# Micro_Card.net
KiCad netlist of a schematic drawn in Altium Designer
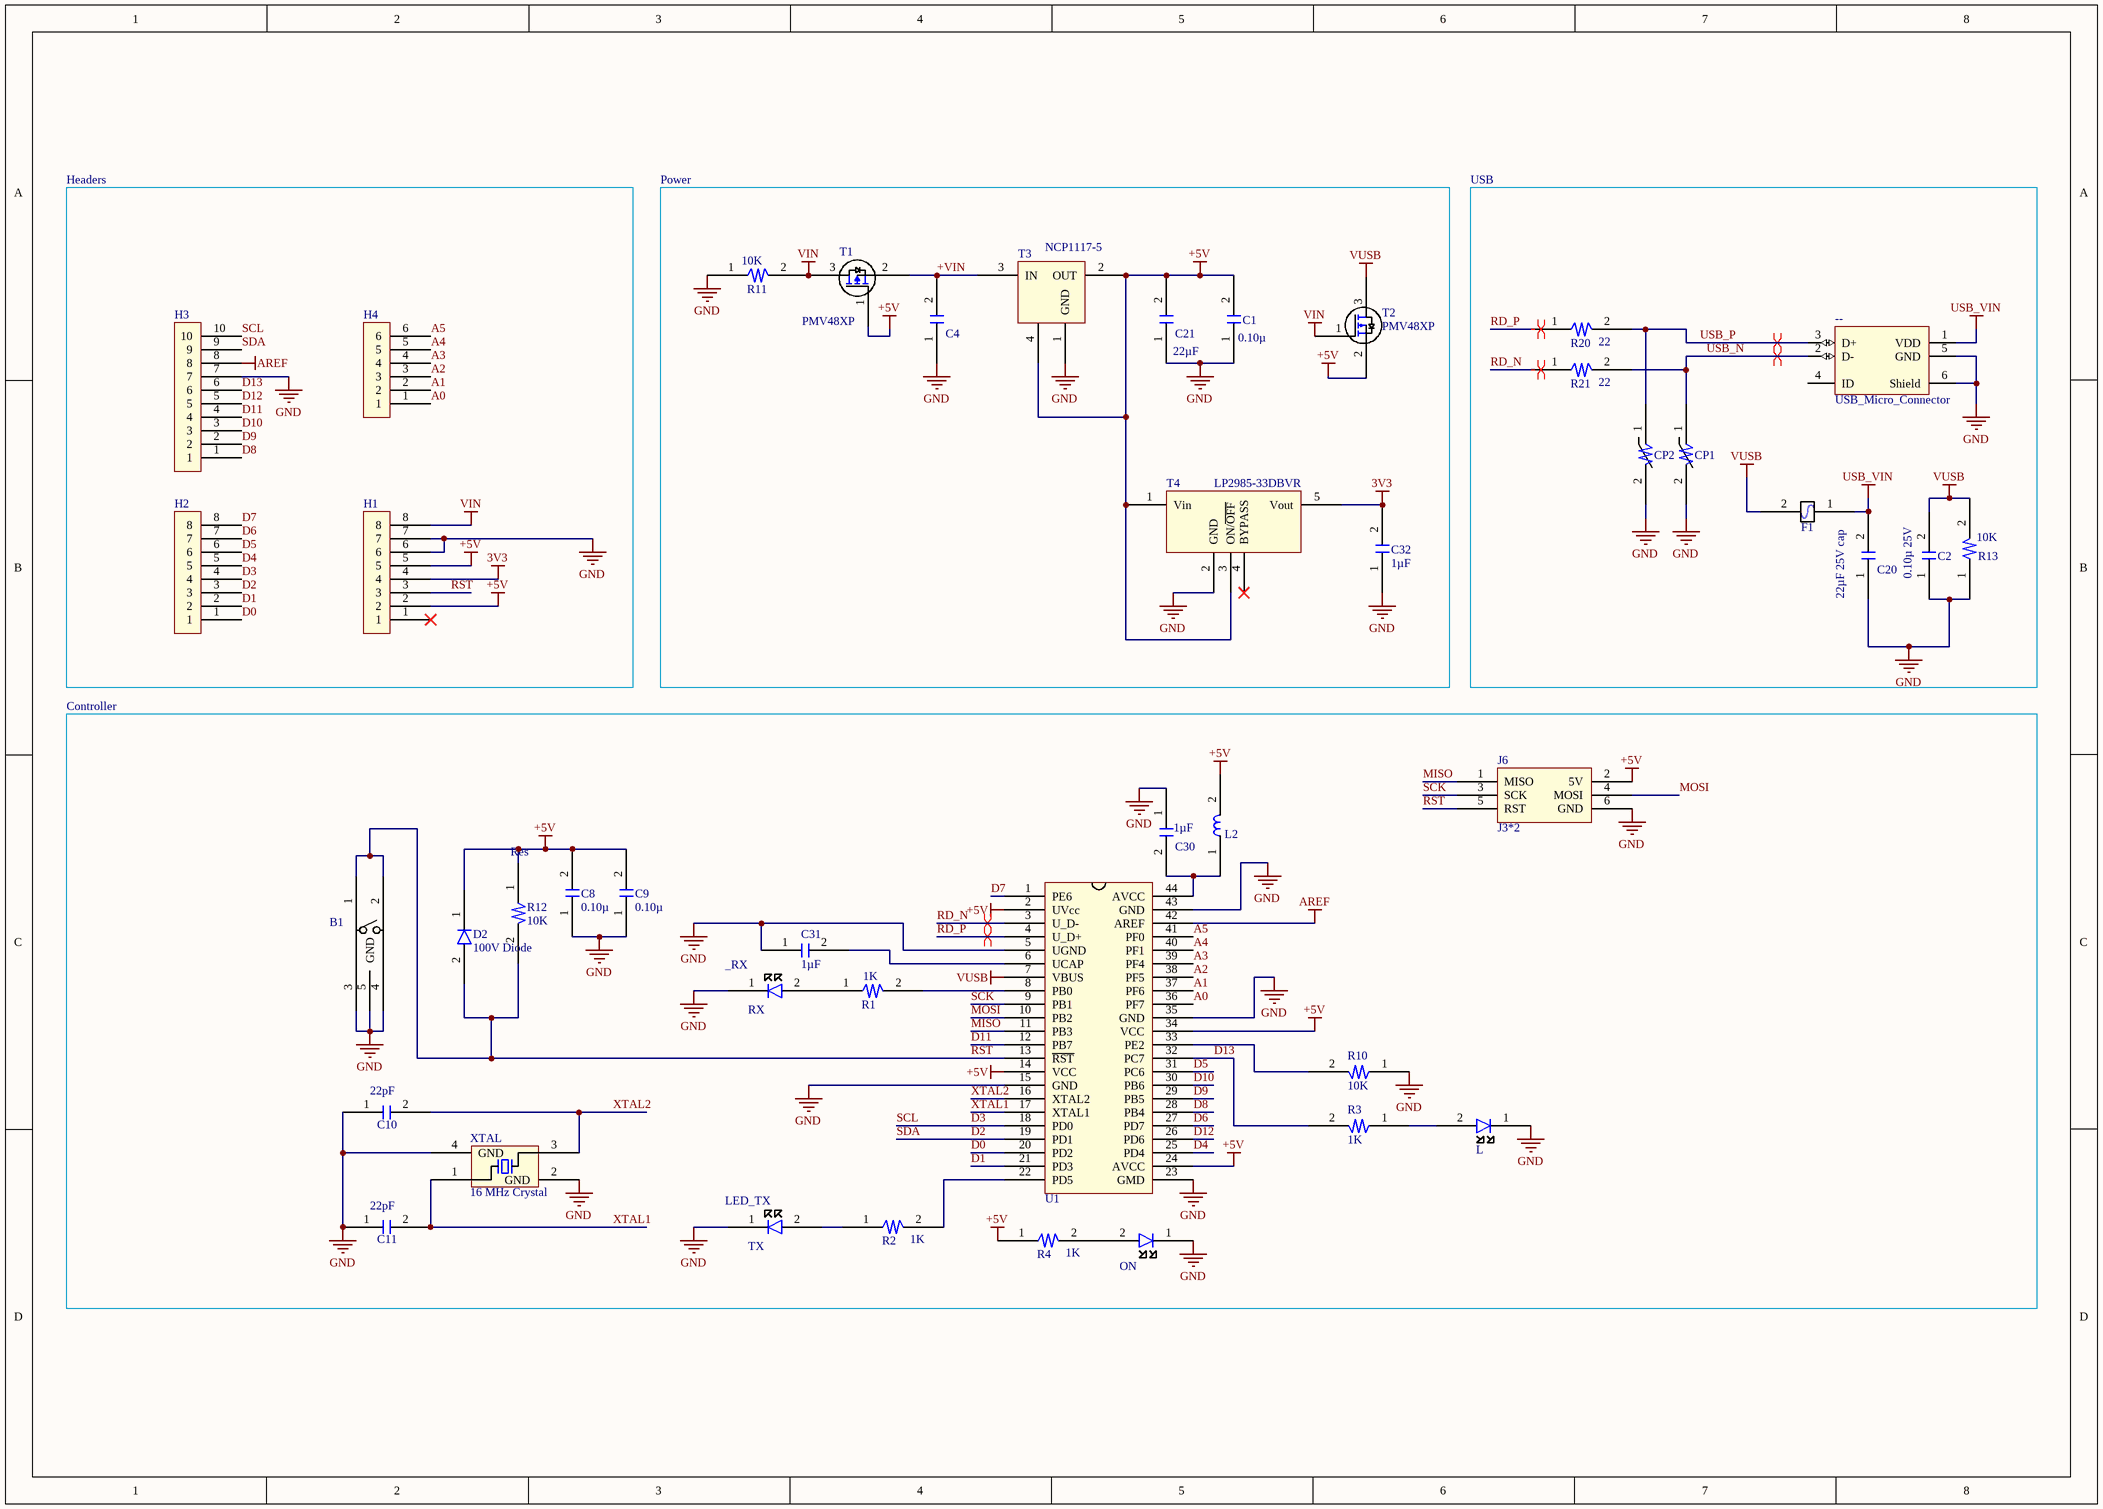
[diagram p0: Micro_Card.SchDoc]

(export (version "E")
  (design (tool "Eeschema 10.0.6"))
  (components
    (comp (ref "--")
      (value "USB_Micro_Connector")
      (footprint "USB_micro_through")
      (description "CONN USB MICRO B RECPT SMT R/A")
      (fields
        (field (name "MANUFACTURER PART NUMBER") "10118194-0001LF")
        (field (name "01 CREATED BY") "David Lynch @ 30/11/2017")
        (field (name "02 REVIEWED BY") "Rodrigo Maureira @ 14/01/2018")
      )
      (libsource (lib "Micro_Schlib") (part "USB_micro_through"))
    )
    (comp (ref "B1")
      (value "off-mom")
      (footprint "450-1760")
      (description "Tactile Button")
      (libsource (lib "Micro_Schlib") (part "Button"))
    )
    (comp (ref "C1")
      (value "0.10µ")
      (footprint "R15_0805_cap_M")
      (description "Cap.")
      (libsource (lib "Micro_Schlib") (part "0.10µF 25V Cap"))
    )
    (comp (ref "C2")
      (value "0.10µ 25V")
      (footprint "R15_0805_cap_M")
      (description "Cap.")
      (libsource (lib "Micro_Schlib") (part "0.10µF 25V Cap"))
    )
    (comp (ref "C4")
      (value "0.10µF ±10% 25V Ceramic Capacitor X7R 0805 (2012 Metric)")
      (footprint "R15_0805_cap_M")
      (description "Cap.")
      (libsource (lib "Micro_Schlib") (part "0.10µF ±10% 25V cap"))
    )
    (comp (ref "C8")
      (value "0.10µ")
      (footprint "R15_0805_cap_M")
      (description "Cap.")
      (libsource (lib "Micro_Schlib") (part "0.10µF 25V Cap"))
    )
    (comp (ref "C9")
      (value "0.10µ")
      (footprint "R15_0805_cap_M")
      (description "Cap.")
      (libsource (lib "Micro_Schlib") (part "0.10µF 25V Cap"))
    )
    (comp (ref "C10")
      (value "22pF")
      (footprint "R15_0805_cap_M")
      (description "Cap.")
      (libsource (lib "Micro_Schlib") (part "22pF 50V cap"))
    )
    (comp (ref "C11")
      (value "22pF")
      (footprint "R15_0805_cap_M")
      (description "Cap.")
      (libsource (lib "Micro_Schlib") (part "22pF 50V cap"))
    )
    (comp (ref "C20")
      (value "22µF 25V cap")
      (footprint "X5R_22uF_25v_1206_X_M")
      (description "Cap.")
      (libsource (lib "Micro_Schlib") (part "22µF 25V cap"))
    )
    (comp (ref "C21")
      (value "22µF")
      (footprint "X5R_22uF_25v_1206_X_M")
      (description "Cap.")
      (libsource (lib "Micro_Schlib") (part "22µF 25V cap"))
    )
    (comp (ref "C30")
      (value "1µF")
      (footprint "C2012_M")
      (description "Cap.")
      (libsource (lib "Micro_Schlib") (part "1µF 50V cap"))
    )
    (comp (ref "C31")
      (value "1µF")
      (footprint "C2012_M")
      (description "Cap.")
      (libsource (lib "Micro_Schlib") (part "1µF 50V cap"))
    )
    (comp (ref "C32")
      (value "1µF")
      (footprint "C2012_M")
      (description "Cap.")
      (libsource (lib "Micro_Schlib") (part "1µF 50V cap"))
    )
    (comp (ref "CP1")
      (value "Gard Resistor")
      (footprint "UltraGuard 0805")
      (libsource (lib "Micro_Schlib") (part "Gard Resistor"))
    )
    (comp (ref "CP2")
      (value "Gard Resistor")
      (footprint "UltraGuard 0805")
      (libsource (lib "Micro_Schlib") (part "Gard Resistor"))
    )
    (comp (ref "D2")
      (value "100V Diode")
      (footprint "CD1206-S01575")
      (description "Standard Diode")
      (libsource (lib "Micro_Schlib") (part "CD1206 - S01575"))
    )
    (comp (ref "F1")
      (value "MF-MSF0502")
      (footprint "MF-MSMF050_M")
      (description "Resetable fuse")
      (libsource (lib "Micro_Schlib") (part "MF-MSF0502"))
    )
    (comp (ref "H1")
      (value "H8")
      (footprint "H8")
      (description "Header")
      (libsource (lib "Micro_Schlib") (part "H8"))
    )
    (comp (ref "H2")
      (value "H8")
      (footprint "H8")
      (description "Header")
      (libsource (lib "Micro_Schlib") (part "H8"))
    )
    (comp (ref "H3")
      (value "H10")
      (footprint "H10")
      (description "Header")
      (libsource (lib "Micro_Schlib") (part "H10"))
    )
    (comp (ref "H4")
      (value "H6")
      (footprint "H6")
      (description "Header")
      (libsource (lib "Micro_Schlib") (part "H6"))
    )
    (comp (ref "J6")
      (value "J3*2")
      (footprint "J3*2")
      (description "Header")
      (libsource (lib "Micro_Schlib") (part "J3*2"))
    )
    (comp (ref "L")
      (value "LED_L")
      (footprint "Wurth led 0805")
      (description "LED clear")
      (libsource (lib "Micro_Schlib") (part "LED"))
    )
    (comp (ref "L2")
      (value "MH2029 - 300Y")
      (footprint "MH2029-300YC")
      (description "Ferite Bead")
      (libsource (lib "Micro_Schlib") (part "MH2029 - 300Y"))
    )
    (comp (ref "ON")
      (value "LED_ON")
      (footprint "Wurth led 0805")
      (description "LED clear")
      (libsource (lib "Micro_Schlib") (part "LED"))
    )
    (comp (ref "R1")
      (value "1K")
      (footprint "RNCP0805_M")
      (description "Res.")
      (fields (field (name "Comment") "Res"))
      (libsource (lib "Micro_Schlib") (part "Res"))
    )
    (comp (ref "R2")
      (value "1K")
      (footprint "RNCP0805_M")
      (description "Res.")
      (fields (field (name "Comment") "Res"))
      (libsource (lib "Micro_Schlib") (part "Res"))
    )
    (comp (ref "R3")
      (value "1K")
      (footprint "RNCP0805_M")
      (description "Res.")
      (fields (field (name "Comment") "Res"))
      (libsource (lib "Micro_Schlib") (part "Res"))
    )
    (comp (ref "R4")
      (value "1K")
      (footprint "RNCP0805_M")
      (description "Res.")
      (libsource (lib "Micro_Schlib") (part "Res"))
    )
    (comp (ref "R10")
      (value "10K")
      (footprint "RNCP0805_M")
      (description "Res.")
      (libsource (lib "Micro_Schlib") (part "Res"))
    )
    (comp (ref "R11")
      (value "10K")
      (footprint "RNCP0805_M")
      (description "Res.")
      (fields (field (name "Comment") "Res"))
      (libsource (lib "Micro_Schlib") (part "Res"))
    )
    (comp (ref "R12")
      (value "Res")
      (footprint "RNCP0805_M")
      (description "Res.")
      (fields (field (name "ALTIUM_VALUE") "10K"))
      (libsource (lib "Micro_Schlib") (part "Res"))
    )
    (comp (ref "R13")
      (value "10K")
      (footprint "RNCP0805_M")
      (description "Res.")
      (libsource (lib "Micro_Schlib") (part "Res"))
    )
    (comp (ref "R20")
      (value "22")
      (footprint "RNCP0805_M")
      (description "Res.")
      (libsource (lib "Micro_Schlib") (part "Res"))
    )
    (comp (ref "R21")
      (value "22")
      (footprint "RNCP0805_M")
      (description "Res.")
      (libsource (lib "Micro_Schlib") (part "Res"))
    )
    (comp (ref "RX")
      (value "_RX")
      (footprint "Wurth led 0805")
      (description "LED clear")
      (libsource (lib "Micro_Schlib") (part "LED"))
    )
    (comp (ref "T1")
      (value "PMV48XP")
      (footprint "PMV48XP_SOT23")
      (description "P type MOSFET")
      (libsource (lib "") (part "PMV48XP_1"))
    )
    (comp (ref "T2")
      (value "PMV48XP")
      (footprint "PMV48XP_SOT23")
      (description "P type MOSFET")
      (libsource (lib "Micro_Schlib") (part "PMV48XP"))
    )
    (comp (ref "T3")
      (value "NCP1117-5")
      (footprint "NCP1117_SOT223")
      (description "5V reg")
      (libsource (lib "Micro_Schlib") (part "NCP1117-5"))
    )
    (comp (ref "T4")
      (value "LP2985-33DBVR")
      (footprint "LP2985_SOT23_M")
      (description "3.3V reg")
      (libsource (lib "Micro_Schlib") (part "LP2985-33DBVR"))
    )
    (comp (ref "TX")
      (value "LED_TX")
      (footprint "Wurth led 0805")
      (description "LED clear")
      (libsource (lib "Micro_Schlib") (part "LED"))
    )
    (comp (ref "U1")
      (value "ATmega32U4")
      (footprint "ATmega32u4_TQFP44")
      (libsource (lib "Micro_Schlib") (part "ATmega32U4"))
    )
    (comp (ref "XTAL")
      (value "16 MHz Crystal")
      (footprint "TSX-3225")
      (description "Crystal")
      (libsource (lib "Micro_Schlib") (part "16 MHz Crystal"))
    )
  )
  (nets
    (net (code "1") (name "+5V") (class "Default")
      (node (ref "C1") (pin "2") (pinfunction "2_2") (pintype "passive"))
      (node (ref "C21") (pin "2") (pinfunction "2_2") (pintype "passive"))
      (node (ref "C8") (pin "2") (pinfunction "2_2") (pintype "passive"))
      (node (ref "C9") (pin "2") (pinfunction "2_2") (pintype "passive"))
      (node (ref "D2") (pin "1") (pinfunction "1_1") (pintype "passive"))
      (node (ref "H1") (pin "2") (pinfunction "2_2") (pintype "passive"))
      (node (ref "H1") (pin "5") (pinfunction "5_5") (pintype "passive"))
      (node (ref "J6") (pin "2") (pinfunction "5V_2") (pintype "passive"))
      (node (ref "L2") (pin "2") (pinfunction "2_2") (pintype "passive"))
      (node (ref "R12") (pin "1") (pinfunction "1_1") (pintype "passive"))
      (node (ref "R4") (pin "1") (pinfunction "1_1") (pintype "passive"))
      (node (ref "T1") (pin "1") (pinfunction "G_1") (pintype "passive"))
      (node (ref "T2") (pin "2") (pinfunction "S_2") (pintype "passive"))
      (node (ref "T3") (pin "2") (pinfunction "OUT_2") (pintype "passive"))
      (node (ref "T3") (pin "4") (pinfunction "tab_4") (pintype "passive"))
      (node (ref "T4") (pin "1") (pinfunction "Vin_1") (pintype "passive"))
      (node (ref "T4") (pin "3") (pinfunction "ON/~{OFF}_3") (pintype "passive"))
      (node (ref "U1") (pin "14") (pinfunction "VCC_14") (pintype "passive"))
      (node (ref "U1") (pin "2") (pinfunction "UVcc_2") (pintype "passive"))
      (node (ref "U1") (pin "24") (pinfunction "AVCC_24") (pintype "passive"))
      (node (ref "U1") (pin "34") (pinfunction "VCC_34") (pintype "passive"))
    )
    (net (code "2") (name "/+VIN") (class "Default")
      (node (ref "C4") (pin "2") (pinfunction "2_2") (pintype "passive"))
      (node (ref "T1") (pin "2") (pinfunction "S_2") (pintype "passive"))
      (node (ref "T3") (pin "3") (pinfunction "IN_3") (pintype "passive"))
    )
    (net (code "3") (name "/A0") (class "Default")
      (node (ref "H4") (pin "1") (pinfunction "1_1") (pintype "passive"))
      (node (ref "U1") (pin "36") (pinfunction "PF7_36") (pintype "passive"))
    )
    (net (code "4") (name "/A1") (class "Default")
      (node (ref "H4") (pin "2") (pinfunction "2_2") (pintype "passive"))
      (node (ref "U1") (pin "37") (pinfunction "PF6_37") (pintype "passive"))
    )
    (net (code "5") (name "/A2") (class "Default")
      (node (ref "H4") (pin "3") (pinfunction "3_3") (pintype "passive"))
      (node (ref "U1") (pin "38") (pinfunction "PF5_38") (pintype "passive"))
    )
    (net (code "6") (name "/A3") (class "Default")
      (node (ref "H4") (pin "4") (pinfunction "4_4") (pintype "passive"))
      (node (ref "U1") (pin "39") (pinfunction "PF4_39") (pintype "passive"))
    )
    (net (code "7") (name "/A4") (class "Default")
      (node (ref "H4") (pin "5") (pinfunction "5_5") (pintype "passive"))
      (node (ref "U1") (pin "40") (pinfunction "PF1_40") (pintype "passive"))
    )
    (net (code "8") (name "/A5") (class "Default")
      (node (ref "H4") (pin "6") (pinfunction "6_6") (pintype "passive"))
      (node (ref "U1") (pin "41") (pinfunction "PF0_41") (pintype "passive"))
    )
    (net (code "9") (name "/D0") (class "Default")
      (node (ref "H2") (pin "1") (pinfunction "1_1") (pintype "passive"))
      (node (ref "U1") (pin "20") (pinfunction "PD2_20") (pintype "passive"))
    )
    (net (code "10") (name "/D1") (class "Default")
      (node (ref "H2") (pin "2") (pinfunction "2_2") (pintype "passive"))
      (node (ref "U1") (pin "21") (pinfunction "PD3_21") (pintype "passive"))
    )
    (net (code "11") (name "/D2") (class "Default")
      (node (ref "H2") (pin "3") (pinfunction "3_3") (pintype "passive"))
      (node (ref "H3") (pin "9") (pinfunction "9_9") (pintype "passive"))
      (node (ref "U1") (pin "19") (pinfunction "PD1_19") (pintype "passive"))
    )
    (net (code "12") (name "/D3") (class "Default")
      (node (ref "H2") (pin "4") (pinfunction "4_4") (pintype "passive"))
      (node (ref "H3") (pin "10") (pinfunction "10_10") (pintype "passive"))
      (node (ref "U1") (pin "18") (pinfunction "PD0_18") (pintype "passive"))
    )
    (net (code "13") (name "/D4") (class "Default")
      (node (ref "H2") (pin "5") (pinfunction "5_5") (pintype "passive"))
      (node (ref "U1") (pin "25") (pinfunction "PD4_25") (pintype "passive"))
    )
    (net (code "14") (name "/D5") (class "Default")
      (node (ref "H2") (pin "6") (pinfunction "6_6") (pintype "passive"))
      (node (ref "U1") (pin "31") (pinfunction "PC6_31") (pintype "passive"))
    )
    (net (code "15") (name "/D6") (class "Default")
      (node (ref "H2") (pin "7") (pinfunction "7_7") (pintype "passive"))
      (node (ref "U1") (pin "27") (pinfunction "PD7_27") (pintype "passive"))
    )
    (net (code "16") (name "/D7") (class "Default")
      (node (ref "H2") (pin "8") (pinfunction "8_8") (pintype "passive"))
      (node (ref "U1") (pin "1") (pinfunction "PE6_1") (pintype "passive"))
    )
    (net (code "17") (name "/D8") (class "Default")
      (node (ref "H3") (pin "1") (pinfunction "1_1") (pintype "passive"))
      (node (ref "U1") (pin "28") (pinfunction "PB4_28") (pintype "passive"))
    )
    (net (code "18") (name "/D9") (class "Default")
      (node (ref "H3") (pin "2") (pinfunction "2_2") (pintype "passive"))
      (node (ref "U1") (pin "29") (pinfunction "PB5_29") (pintype "passive"))
    )
    (net (code "19") (name "/D10") (class "Default")
      (node (ref "H3") (pin "3") (pinfunction "3_3") (pintype "passive"))
      (node (ref "U1") (pin "30") (pinfunction "PB6_30") (pintype "passive"))
    )
    (net (code "20") (name "/D11") (class "Default")
      (node (ref "H3") (pin "4") (pinfunction "4_4") (pintype "passive"))
      (node (ref "U1") (pin "12") (pinfunction "PB7_12") (pintype "passive"))
    )
    (net (code "21") (name "/D12") (class "Default")
      (node (ref "H3") (pin "5") (pinfunction "5_5") (pintype "passive"))
      (node (ref "U1") (pin "26") (pinfunction "PD6_26") (pintype "passive"))
    )
    (net (code "22") (name "/D13") (class "Default")
      (node (ref "H3") (pin "6") (pinfunction "6_6") (pintype "passive"))
      (node (ref "R3") (pin "2") (pinfunction "2_2") (pintype "passive"))
      (node (ref "U1") (pin "32") (pinfunction "PC7_32") (pintype "passive"))
    )
    (net (code "23") (name "/MISO") (class "Default")
      (node (ref "J6") (pin "1") (pinfunction "MISO_1") (pintype "passive"))
      (node (ref "U1") (pin "11") (pinfunction "PB3_11") (pintype "passive"))
    )
    (net (code "24") (name "/MOSI") (class "Default")
      (node (ref "J6") (pin "4") (pinfunction "MOSI_4") (pintype "passive"))
      (node (ref "U1") (pin "10") (pinfunction "PB2_10") (pintype "passive"))
    )
    (net (code "25") (name "/RD_N") (class "Default")
      (node (ref "R21") (pin "1") (pinfunction "1_1") (pintype "passive"))
      (node (ref "U1") (pin "3") (pinfunction "U_D-_3") (pintype "passive"))
    )
    (net (code "26") (name "/RD_P") (class "Default")
      (node (ref "R20") (pin "1") (pinfunction "1_1") (pintype "passive"))
      (node (ref "U1") (pin "4") (pinfunction "U_D+_4") (pintype "passive"))
    )
    (net (code "27") (name "/RST") (class "Default")
      (node (ref "B1") (pin "1") (pinfunction "1_1") (pintype "passive"))
      (node (ref "B1") (pin "2") (pinfunction "2_2") (pintype "passive"))
      (node (ref "D2") (pin "2") (pinfunction "2_2") (pintype "passive"))
      (node (ref "H1") (pin "3") (pinfunction "3_3") (pintype "passive"))
      (node (ref "J6") (pin "5") (pinfunction "RST_5") (pintype "passive"))
      (node (ref "R12") (pin "2") (pinfunction "2_2") (pintype "passive"))
      (node (ref "U1") (pin "13") (pinfunction "~{RST}_13") (pintype "passive"))
    )
    (net (code "28") (name "/SCK") (class "Default")
      (node (ref "J6") (pin "3") (pinfunction "SCK_3") (pintype "passive"))
      (node (ref "U1") (pin "9") (pinfunction "PB1_9") (pintype "passive"))
    )
    (net (code "29") (name "/USB_N") (class "Default")
      (node (ref "--") (pin "2") (pinfunction "D-_2") (pintype "bidirectional"))
      (node (ref "CP1") (pin "1") (pinfunction "1_1") (pintype "passive"))
      (node (ref "R21") (pin "2") (pinfunction "2_2") (pintype "passive"))
    )
    (net (code "30") (name "/USB_P") (class "Default")
      (node (ref "--") (pin "3") (pinfunction "D+_3") (pintype "bidirectional"))
      (node (ref "CP2") (pin "1") (pinfunction "1_1") (pintype "passive"))
      (node (ref "R20") (pin "2") (pinfunction "2_2") (pintype "passive"))
    )
    (net (code "31") (name "/XTAL1") (class "Default")
      (node (ref "C11") (pin "2") (pinfunction "2_2") (pintype "passive"))
      (node (ref "U1") (pin "17") (pinfunction "XTAL1_17") (pintype "passive"))
      (node (ref "XTAL") (pin "1") (pinfunction "1_1") (pintype "passive"))
    )
    (net (code "32") (name "/XTAL2") (class "Default")
      (node (ref "C10") (pin "2") (pinfunction "2_2") (pintype "passive"))
      (node (ref "U1") (pin "16") (pinfunction "XTAL2_16") (pintype "passive"))
      (node (ref "XTAL") (pin "3") (pinfunction "3_3") (pintype "passive"))
    )
    (net (code "33") (name "3V3") (class "Default")
      (node (ref "C32") (pin "2") (pinfunction "2_2") (pintype "passive"))
      (node (ref "H1") (pin "4") (pinfunction "4_4") (pintype "passive"))
      (node (ref "T4") (pin "5") (pinfunction "Vout_5") (pintype "passive"))
    )
    (net (code "34") (name "AREF") (class "Default")
      (node (ref "H3") (pin "8") (pinfunction "8_8") (pintype "passive"))
      (node (ref "U1") (pin "42") (pinfunction "AREF_42") (pintype "passive"))
    )
    (net (code "35") (name "GND") (class "Default")
      (node (ref "--") (pin "5") (pinfunction "GND_5") (pintype "power_in"))
      (node (ref "--") (pin "6") (pinfunction "Shield_6") (pintype "passive"))
      (node (ref "B1") (pin "3") (pinfunction "3_3") (pintype "passive"))
      (node (ref "B1") (pin "4") (pinfunction "4_4") (pintype "passive"))
      (node (ref "B1") (pin "5") (pinfunction "GND_5") (pintype "passive"))
      (node (ref "C1") (pin "1") (pinfunction "1_1") (pintype "passive"))
      (node (ref "C10") (pin "1") (pinfunction "1_1") (pintype "passive"))
      (node (ref "C11") (pin "1") (pinfunction "1_1") (pintype "passive"))
      (node (ref "C2") (pin "1") (pinfunction "1_1") (pintype "passive"))
      (node (ref "C20") (pin "1") (pinfunction "1_1") (pintype "passive"))
      (node (ref "C21") (pin "1") (pinfunction "1_1") (pintype "passive"))
      (node (ref "C30") (pin "1") (pinfunction "1_1") (pintype "passive"))
      (node (ref "C31") (pin "1") (pinfunction "1_1") (pintype "passive"))
      (node (ref "C32") (pin "1") (pinfunction "1_1") (pintype "passive"))
      (node (ref "C4") (pin "1") (pinfunction "1_1") (pintype "passive"))
      (node (ref "C8") (pin "1") (pinfunction "1_1") (pintype "passive"))
      (node (ref "C9") (pin "1") (pinfunction "1_1") (pintype "passive"))
      (node (ref "CP1") (pin "2") (pinfunction "2_2") (pintype "passive"))
      (node (ref "CP2") (pin "2") (pinfunction "2_2") (pintype "passive"))
      (node (ref "H1") (pin "6") (pinfunction "6_6") (pintype "passive"))
      (node (ref "H1") (pin "7") (pinfunction "7_7") (pintype "passive"))
      (node (ref "H3") (pin "7") (pinfunction "7_7") (pintype "passive"))
      (node (ref "J6") (pin "6") (pinfunction "GND_6") (pintype "passive"))
      (node (ref "L") (pin "1") (pinfunction "1_1") (pintype "passive"))
      (node (ref "ON") (pin "1") (pinfunction "1_1") (pintype "passive"))
      (node (ref "R10") (pin "1") (pinfunction "1_1") (pintype "passive"))
      (node (ref "R11") (pin "1") (pinfunction "1_1") (pintype "passive"))
      (node (ref "R13") (pin "1") (pinfunction "1_1") (pintype "passive"))
      (node (ref "RX") (pin "1") (pinfunction "1_1") (pintype "passive"))
      (node (ref "T3") (pin "1") (pinfunction "GND_1") (pintype "passive"))
      (node (ref "T4") (pin "2") (pinfunction "GND_2") (pintype "passive"))
      (node (ref "TX") (pin "1") (pinfunction "1_1") (pintype "passive"))
      (node (ref "U1") (pin "15") (pinfunction "GND_15") (pintype "passive"))
      (node (ref "U1") (pin "23") (pinfunction "GMD_23") (pintype "passive"))
      (node (ref "U1") (pin "35") (pinfunction "GND_35") (pintype "passive"))
      (node (ref "U1") (pin "43") (pinfunction "GND_43") (pintype "passive"))
      (node (ref "U1") (pin "5") (pinfunction "UGND_5") (pintype "passive"))
      (node (ref "XTAL") (pin "2") (pinfunction "GND_2") (pintype "passive"))
      (node (ref "XTAL") (pin "4") (pinfunction "GND_4") (pintype "passive"))
    )
    (net (code "36") (name "Net-(C30-Pad2)") (class "Default")
      (node (ref "C30") (pin "2") (pinfunction "2_2") (pintype "passive"))
      (node (ref "L2") (pin "1") (pinfunction "1_1") (pintype "passive"))
      (node (ref "U1") (pin "44") (pinfunction "AVCC_44") (pintype "passive"))
    )
    (net (code "37") (name "Net-(L-Pad2)") (class "Default")
      (node (ref "L") (pin "2") (pinfunction "2_2") (pintype "passive"))
      (node (ref "R3") (pin "1") (pinfunction "1_1") (pintype "passive"))
    )
    (net (code "38") (name "Net-(ON-Pad2)") (class "Default")
      (node (ref "ON") (pin "2") (pinfunction "2_2") (pintype "passive"))
      (node (ref "R4") (pin "2") (pinfunction "2_2") (pintype "passive"))
    )
    (net (code "39") (name "Net-(R1-Pad1)") (class "Default")
      (node (ref "R1") (pin "1") (pinfunction "1_1") (pintype "passive"))
      (node (ref "RX") (pin "2") (pinfunction "2_2") (pintype "passive"))
    )
    (net (code "40") (name "Net-(R2-Pad1)") (class "Default")
      (node (ref "R2") (pin "1") (pinfunction "1_1") (pintype "passive"))
      (node (ref "TX") (pin "2") (pinfunction "2_2") (pintype "passive"))
    )
    (net (code "41") (name "Net-(U1-PB0)") (class "Default")
      (node (ref "R1") (pin "2") (pinfunction "2_2") (pintype "passive"))
      (node (ref "U1") (pin "8") (pinfunction "PB0_8") (pintype "passive"))
    )
    (net (code "42") (name "Net-(U1-PD5)") (class "Default")
      (node (ref "R2") (pin "2") (pinfunction "2_2") (pintype "passive"))
      (node (ref "U1") (pin "22") (pinfunction "PD5_22") (pintype "passive"))
    )
    (net (code "43") (name "Net-(U1-PE2)") (class "Default")
      (node (ref "R10") (pin "2") (pinfunction "2_2") (pintype "passive"))
      (node (ref "U1") (pin "33") (pinfunction "PE2_33") (pintype "passive"))
    )
    (net (code "44") (name "Net-(U1-UCAP)") (class "Default")
      (node (ref "C31") (pin "2") (pinfunction "2_2") (pintype "passive"))
      (node (ref "U1") (pin "6") (pinfunction "UCAP_6") (pintype "passive"))
    )
    (net (code "45") (name "USB_VIN") (class "Default")
      (node (ref "--") (pin "1") (pinfunction "VDD_1") (pintype "power_in"))
      (node (ref "C20") (pin "2") (pinfunction "2_2") (pintype "passive"))
      (node (ref "F1") (pin "1") (pinfunction "1_1") (pintype "passive"))
    )
    (net (code "46") (name "VIN") (class "Default")
      (node (ref "H1") (pin "8") (pinfunction "8_8") (pintype "passive"))
      (node (ref "R11") (pin "2") (pinfunction "2_2") (pintype "passive"))
      (node (ref "T1") (pin "3") (pinfunction "D_3") (pintype "passive"))
      (node (ref "T2") (pin "1") (pinfunction "G_1") (pintype "passive"))
    )
    (net (code "47") (name "VUSB") (class "Default")
      (node (ref "C2") (pin "2") (pinfunction "2_2") (pintype "passive"))
      (node (ref "F1") (pin "2") (pinfunction "2_2") (pintype "passive"))
      (node (ref "R13") (pin "2") (pinfunction "2_2") (pintype "passive"))
      (node (ref "T2") (pin "3") (pinfunction "D_3") (pintype "passive"))
      (node (ref "U1") (pin "7") (pinfunction "VBUS_7") (pintype "passive"))
    )
    (net (code "48") (name "unconnected-(---ID-Pad4)") (class "Default")
      (node (ref "--") (pin "4") (pinfunction "ID_4") (pintype "passive"))
    )
    (net (code "49") (name "unconnected-(H1-Pad1)") (class "Default")
      (node (ref "H1") (pin "1") (pinfunction "1_1") (pintype "passive+no_connect"))
    )
    (net (code "50") (name "unconnected-(T4-BYPASS-Pad4)") (class "Default")
      (node (ref "T4") (pin "4") (pinfunction "BYPASS_4") (pintype "passive+no_connect"))
    )
  )
)
